# LTE_auto_start_Rev01.net
KiCad netlist of a schematic drawn in Altium Designer
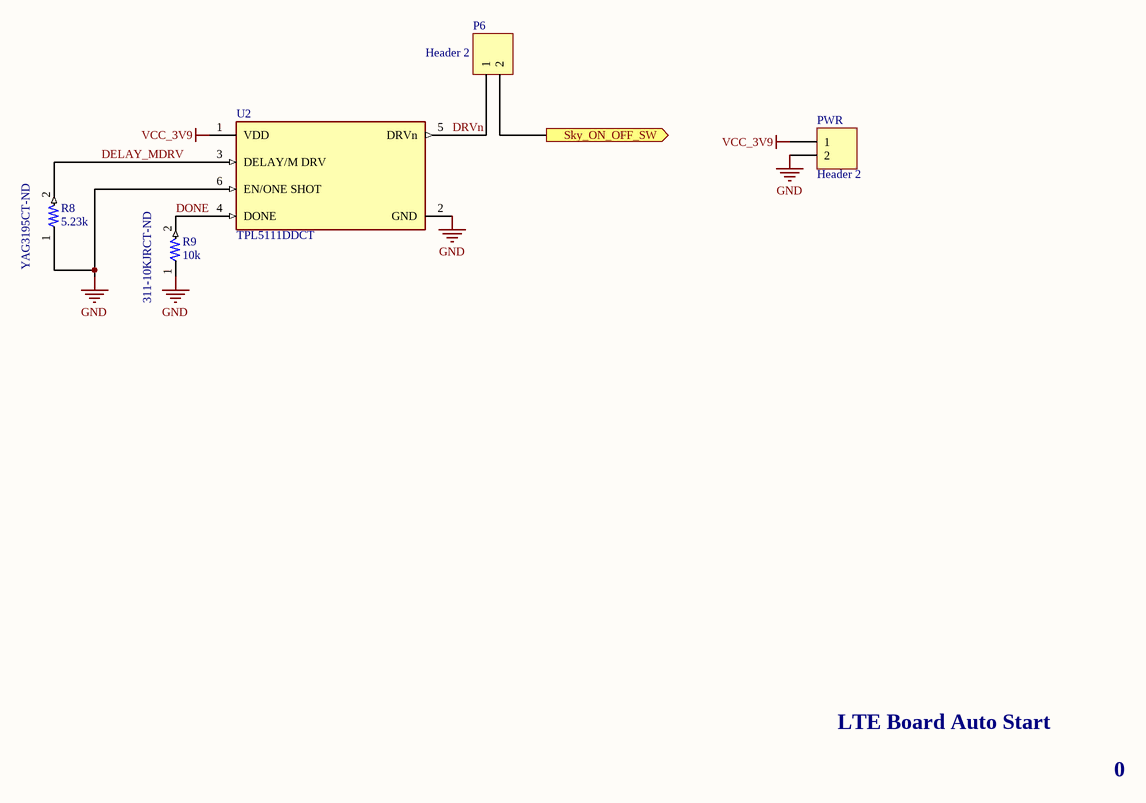
[diagram p0: LTE_auto_start_Rev01.SchDoc]

(export (version "E")
  (design (tool "Eeschema 10.0.6"))
  (components
    (comp (ref "P6")
      (value "Header 2")
      (footprint "HDR1X2")
      (description "Header, 2-Pin")
      (fields (field (name "PUBLISHER") "Altium Limited"))
      (libsource (lib "Miscellaneous Connectors") (part "Header 2"))
    )
    (comp (ref "PWR")
      (value "Header 2")
      (footprint "Wire_entry_200mil")
      (description "Header, 2-Pin")
      (fields (field (name "PUBLISHER") "Altium Limited"))
      (libsource (lib "") (part "Header 2_1"))
    )
    (comp (ref "R8")
      (value "YAG3195CT-ND")
      (footprint "SMD RES 1005")
      (description "5.23 kOhms ±1% 0.063W, 1/16W Chip Resistor 0402 (1005 Metric) Moisture Resistant Thick Film")
      (fields
        (field (name "PART_NUMBER") "YAG3195CT-ND")
        (field (name "RESISTANCE_OHMS") "5.23k")
        (field (name "POWER") "0.063W, 1/16W")
        (field (name "TOLERANCE") "±1%")
      )
      (libsource (lib "AltiumProductionDatabase") (part "R, 1K, 1%, 1/16W, 0402"))
    )
    (comp (ref "R9")
      (value "RC0402JR-0710KL")
      (footprint "SMD RES 1005")
      (description "10 kOhms ±5% 0.063W, 1/16W Chip Resistor 0402 (1005 Metric) Moisture Resistant Thick Film")
      (fields
        (field (name "PART_NUMBER") "311-10KJRCT-ND")
        (field (name "RESISTANCE_OHMS") "10k")
        (field (name "POWER") "0.063W, 1/16W")
        (field (name "TOLERANCE") "±1%")
      )
      (libsource (lib "AltiumProductionDatabase") (part "R, 1K, 1%, 1/16W, 0402"))
    )
    (comp (ref "U2")
      (value "TPL5111DDCT")
      (footprint "FP-DDC0006A-IPC_B")
      (description "IC OSC PROG TIMER TSOT23-6")
      (fields
        (field (name "DIGI-KEY PART NUMBER") "296-42621-1-ND")
        (field (name "MANUFACTURER") "Texas Instruments")
      )
      (libsource (lib "Altium Content Vault") (part "b762ea427669d011917c02059d2a29e"))
    )
  )
  (nets
    (net (code "1") (name "/DELAY_MDRV") (class "Default")
      (node (ref "R8") (pin "2") (pinfunction "2_2") (pintype "output"))
      (node (ref "U2") (pin "3") (pinfunction "DELAY/M_DRV_3") (pintype "input"))
    )
    (net (code "2") (name "/DONE") (class "Default")
      (node (ref "R9") (pin "2") (pinfunction "2_2") (pintype "output"))
      (node (ref "U2") (pin "4") (pinfunction "DONE_4") (pintype "input"))
    )
    (net (code "3") (name "/DRVn") (class "Default")
      (node (ref "P6") (pin "1") (pinfunction "1_1") (pintype "passive"))
      (node (ref "U2") (pin "5") (pinfunction "DRVn_5") (pintype "output"))
    )
    (net (code "4") (name "/Sky_ON_OFF_SW") (class "Default")
      (node (ref "P6") (pin "2") (pinfunction "2_2") (pintype "passive"))
    )
    (net (code "5") (name "GND") (class "Default")
      (node (ref "PWR") (pin "2") (pinfunction "2_2") (pintype "passive"))
      (node (ref "R8") (pin "1") (pinfunction "1_1") (pintype "passive"))
      (node (ref "R9") (pin "1") (pinfunction "1_1") (pintype "passive"))
      (node (ref "U2") (pin "2") (pinfunction "GND_2") (pintype "power_in"))
      (node (ref "U2") (pin "6") (pinfunction "EN/ONE_SHOT_6") (pintype "input"))
    )
    (net (code "6") (name "VCC_3V9") (class "Default")
      (node (ref "PWR") (pin "1") (pinfunction "1_1") (pintype "passive"))
      (node (ref "U2") (pin "1") (pinfunction "VDD_1") (pintype "power_in"))
    )
  )
)
